# FPGA_Banks.net
KiCad netlist of a schematic drawn in Altium Designer
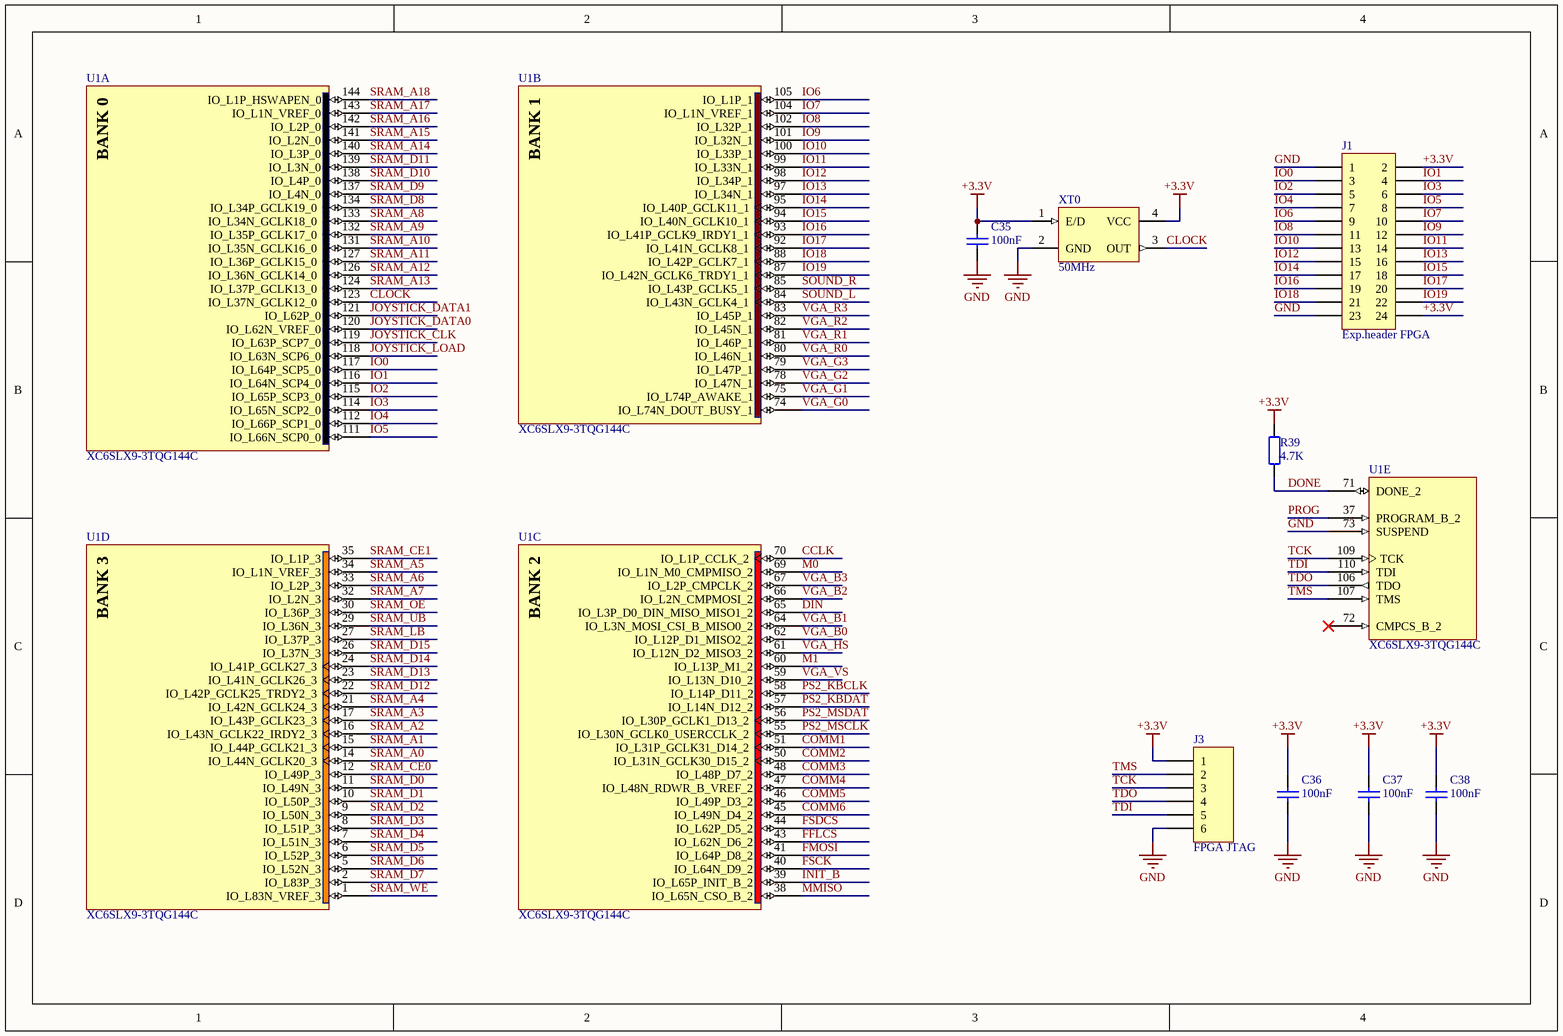
[diagram p0: FPGA Banks.SchDoc]

(export (version "E")
  (design (tool "Eeschema 10.0.6"))
  (components
    (comp (ref "C35")
      (value "100nF")
      (footprint "6-0805_n")
      (description "Capacitor")
      (fields (field (name "Comment") "Cap") (field (name "PUBLISHER") "Altium Limited"))
      (libsource (lib "Miscellaneous Devices") (part "Cap"))
    )
    (comp (ref "C36")
      (value "100nF")
      (footprint "6-0805_n")
      (description "Capacitor")
      (fields (field (name "Comment") "Cap") (field (name "PUBLISHER") "Altium Limited"))
      (libsource (lib "Miscellaneous Devices") (part "Cap"))
    )
    (comp (ref "C37")
      (value "100nF")
      (footprint "6-0805_n")
      (description "Capacitor")
      (fields (field (name "Comment") "Cap") (field (name "PUBLISHER") "Altium Limited"))
      (libsource (lib "Miscellaneous Devices") (part "Cap"))
    )
    (comp (ref "C38")
      (value "100nF")
      (footprint "6-0805_n")
      (description "Capacitor")
      (fields (field (name "Comment") "Cap") (field (name "PUBLISHER") "Altium Limited"))
      (libsource (lib "Miscellaneous Devices") (part "Cap"))
    )
    (comp (ref "J1")
      (value "Exp.header FPGA")
      (footprint "HDR2X12")
      (description "Header, 12-Pin, Dual row")
      (fields (field (name "PUBLISHER") "Altium Limited"))
      (libsource (lib "Miscellaneous Connectors") (part "Header 12X2"))
    )
    (comp (ref "J3")
      (value "FPGA JTAG")
      (footprint "HDR1X6")
      (description "Header, 6-Pin")
      (fields (field (name "PUBLISHER") "Altium Limited"))
      (libsource (lib "Miscellaneous Connectors") (part "Header 6"))
    )
    (comp (ref "R39")
      (value "4.7K")
      (footprint "6-0805_N")
      (description "Resistor")
      (fields (field (name "Comment") "Res2") (field (name "PUBLISHER") "Altium Limited"))
      (libsource (lib "Miscellaneous Devices") (part "Res2"))
    )
    (comp (ref "U1")
      (value "XC6SLX9-3TQG144C")
      (footprint "TQG144_N")
      (fields (field (name "PUBLISHER") "Altium Limited"))
      (libsource (lib "Xilinx Spartan-6") (part "XC6SLX9-3TQG144C"))
    )
    (comp (ref "XT0")
      (value "50MHz")
      (footprint "Oscillator SMD 7x5mm")
      (fields (field (name "Comment") "Oscillator"))
      (libsource (lib "Passiv") (part "Oscillator"))
    )
  )
  (nets
    (net (code "1") (name "+3.3V") (class "Default")
      (node (ref "C35") (pin "2") (pinfunction "2_2") (pintype "passive"))
      (node (ref "C36") (pin "2") (pinfunction "2_2") (pintype "passive"))
      (node (ref "C37") (pin "2") (pinfunction "2_2") (pintype "passive"))
      (node (ref "C38") (pin "2") (pinfunction "2_2") (pintype "passive"))
      (node (ref "J1") (pin "2") (pinfunction "2_2") (pintype "passive"))
      (node (ref "J1") (pin "24") (pinfunction "24_24") (pintype "passive"))
      (node (ref "J3") (pin "1") (pinfunction "1_1") (pintype "passive"))
      (node (ref "R39") (pin "1") (pinfunction "1_1") (pintype "passive"))
      (node (ref "XT0") (pin "1") (pinfunction "E/D_1") (pintype "input"))
      (node (ref "XT0") (pin "4") (pinfunction "VCC_4") (pintype "passive"))
    )
    (net (code "2") (name "/CCLK") (class "Default")
      (node (ref "U1") (pin "70") (pinfunction "IO_L1P_CCLK_2_70") (pintype "bidirectional"))
    )
    (net (code "3") (name "/CLOCK") (class "Default")
      (node (ref "U1") (pin "123") (pinfunction "IO_L37N_GCLK12_0_123") (pintype "bidirectional"))
      (node (ref "XT0") (pin "3") (pinfunction "OUT_3") (pintype "output"))
    )
    (net (code "4") (name "/COMM1") (class "Default")
      (node (ref "U1") (pin "51") (pinfunction "IO_L31P_GCLK31_D14_2_51") (pintype "bidirectional"))
    )
    (net (code "5") (name "/COMM2") (class "Default")
      (node (ref "U1") (pin "50") (pinfunction "IO_L31N_GCLK30_D15_2_50") (pintype "bidirectional"))
    )
    (net (code "6") (name "/COMM3") (class "Default")
      (node (ref "U1") (pin "48") (pinfunction "IO_L48P_D7_2_48") (pintype "bidirectional"))
    )
    (net (code "7") (name "/COMM4") (class "Default")
      (node (ref "U1") (pin "47") (pinfunction "IO_L48N_RDWR_B_VREF_2_47") (pintype "bidirectional"))
    )
    (net (code "8") (name "/COMM5") (class "Default")
      (node (ref "U1") (pin "46") (pinfunction "IO_L49P_D3_2_46") (pintype "bidirectional"))
    )
    (net (code "9") (name "/COMM6") (class "Default")
      (node (ref "U1") (pin "45") (pinfunction "IO_L49N_D4_2_45") (pintype "bidirectional"))
    )
    (net (code "10") (name "/DIN") (class "Default")
      (node (ref "U1") (pin "65") (pinfunction "IO_L3P_D0_DIN_MISO_MISO1_2_65") (pintype "bidirectional"))
    )
    (net (code "11") (name "/DONE") (class "Default")
      (node (ref "R39") (pin "2") (pinfunction "2_2") (pintype "passive"))
      (node (ref "U1") (pin "71") (pinfunction "DONE_2_71") (pintype "bidirectional"))
    )
    (net (code "12") (name "/FFLCS") (class "Default")
      (node (ref "U1") (pin "43") (pinfunction "IO_L62N_D6_2_43") (pintype "bidirectional"))
    )
    (net (code "13") (name "/FMOSI") (class "Default")
      (node (ref "U1") (pin "41") (pinfunction "IO_L64P_D8_2_41") (pintype "bidirectional"))
    )
    (net (code "14") (name "/FSCK") (class "Default")
      (node (ref "U1") (pin "40") (pinfunction "IO_L64N_D9_2_40") (pintype "bidirectional"))
    )
    (net (code "15") (name "/FSDCS") (class "Default")
      (node (ref "U1") (pin "44") (pinfunction "IO_L62P_D5_2_44") (pintype "bidirectional"))
    )
    (net (code "16") (name "/INIT_B") (class "Default")
      (node (ref "U1") (pin "39") (pinfunction "IO_L65P_INIT_B_2_39") (pintype "bidirectional"))
    )
    (net (code "17") (name "/IO0") (class "Default")
      (node (ref "J1") (pin "3") (pinfunction "3_3") (pintype "passive"))
      (node (ref "U1") (pin "117") (pinfunction "IO_L64P_SCP5_0_117") (pintype "bidirectional"))
    )
    (net (code "18") (name "/IO1") (class "Default")
      (node (ref "J1") (pin "4") (pinfunction "4_4") (pintype "passive"))
      (node (ref "U1") (pin "116") (pinfunction "IO_L64N_SCP4_0_116") (pintype "bidirectional"))
    )
    (net (code "19") (name "/IO2") (class "Default")
      (node (ref "J1") (pin "5") (pinfunction "5_5") (pintype "passive"))
      (node (ref "U1") (pin "115") (pinfunction "IO_L65P_SCP3_0_115") (pintype "bidirectional"))
    )
    (net (code "20") (name "/IO3") (class "Default")
      (node (ref "J1") (pin "6") (pinfunction "6_6") (pintype "passive"))
      (node (ref "U1") (pin "114") (pinfunction "IO_L65N_SCP2_0_114") (pintype "bidirectional"))
    )
    (net (code "21") (name "/IO4") (class "Default")
      (node (ref "J1") (pin "7") (pinfunction "7_7") (pintype "passive"))
      (node (ref "U1") (pin "112") (pinfunction "IO_L66P_SCP1_0_112") (pintype "bidirectional"))
    )
    (net (code "22") (name "/IO5") (class "Default")
      (node (ref "J1") (pin "8") (pinfunction "8_8") (pintype "passive"))
      (node (ref "U1") (pin "111") (pinfunction "IO_L66N_SCP0_0_111") (pintype "bidirectional"))
    )
    (net (code "23") (name "/IO6") (class "Default")
      (node (ref "J1") (pin "9") (pinfunction "9_9") (pintype "passive"))
      (node (ref "U1") (pin "105") (pinfunction "IO_L1P_1_105") (pintype "bidirectional"))
    )
    (net (code "24") (name "/IO7") (class "Default")
      (node (ref "J1") (pin "10") (pinfunction "10_10") (pintype "passive"))
      (node (ref "U1") (pin "104") (pinfunction "IO_L1N_VREF_1_104") (pintype "bidirectional"))
    )
    (net (code "25") (name "/IO8") (class "Default")
      (node (ref "J1") (pin "11") (pinfunction "11_11") (pintype "passive"))
      (node (ref "U1") (pin "102") (pinfunction "IO_L32P_1_102") (pintype "bidirectional"))
    )
    (net (code "26") (name "/IO9") (class "Default")
      (node (ref "J1") (pin "12") (pinfunction "12_12") (pintype "passive"))
      (node (ref "U1") (pin "101") (pinfunction "IO_L32N_1_101") (pintype "bidirectional"))
    )
    (net (code "27") (name "/IO10") (class "Default")
      (node (ref "J1") (pin "13") (pinfunction "13_13") (pintype "passive"))
      (node (ref "U1") (pin "100") (pinfunction "IO_L33P_1_100") (pintype "bidirectional"))
    )
    (net (code "28") (name "/IO11") (class "Default")
      (node (ref "J1") (pin "14") (pinfunction "14_14") (pintype "passive"))
      (node (ref "U1") (pin "99") (pinfunction "IO_L33N_1_99") (pintype "bidirectional"))
    )
    (net (code "29") (name "/IO12") (class "Default")
      (node (ref "J1") (pin "15") (pinfunction "15_15") (pintype "passive"))
      (node (ref "U1") (pin "98") (pinfunction "IO_L34P_1_98") (pintype "bidirectional"))
    )
    (net (code "30") (name "/IO13") (class "Default")
      (node (ref "J1") (pin "16") (pinfunction "16_16") (pintype "passive"))
      (node (ref "U1") (pin "97") (pinfunction "IO_L34N_1_97") (pintype "bidirectional"))
    )
    (net (code "31") (name "/IO14") (class "Default")
      (node (ref "J1") (pin "17") (pinfunction "17_17") (pintype "passive"))
      (node (ref "U1") (pin "95") (pinfunction "IO_L40P_GCLK11_1_95") (pintype "bidirectional"))
    )
    (net (code "32") (name "/IO15") (class "Default")
      (node (ref "J1") (pin "18") (pinfunction "18_18") (pintype "passive"))
      (node (ref "U1") (pin "94") (pinfunction "IO_L40N_GCLK10_1_94") (pintype "bidirectional"))
    )
    (net (code "33") (name "/IO16") (class "Default")
      (node (ref "J1") (pin "19") (pinfunction "19_19") (pintype "passive"))
      (node (ref "U1") (pin "93") (pinfunction "IO_L41P_GCLK9_IRDY1_1_93") (pintype "bidirectional"))
    )
    (net (code "34") (name "/IO17") (class "Default")
      (node (ref "J1") (pin "20") (pinfunction "20_20") (pintype "passive"))
      (node (ref "U1") (pin "92") (pinfunction "IO_L41N_GCLK8_1_92") (pintype "bidirectional"))
    )
    (net (code "35") (name "/IO18") (class "Default")
      (node (ref "J1") (pin "21") (pinfunction "21_21") (pintype "passive"))
      (node (ref "U1") (pin "88") (pinfunction "IO_L42P_GCLK7_1_88") (pintype "bidirectional"))
    )
    (net (code "36") (name "/IO19") (class "Default")
      (node (ref "J1") (pin "22") (pinfunction "22_22") (pintype "passive"))
      (node (ref "U1") (pin "87") (pinfunction "IO_L42N_GCLK6_TRDY1_1_87") (pintype "bidirectional"))
    )
    (net (code "37") (name "/JOYSTICK_CLK") (class "Default")
      (node (ref "U1") (pin "119") (pinfunction "IO_L63P_SCP7_0_119") (pintype "bidirectional"))
    )
    (net (code "38") (name "/JOYSTICK_DATA0") (class "Default")
      (node (ref "U1") (pin "120") (pinfunction "IO_L62N_VREF_0_120") (pintype "bidirectional"))
    )
    (net (code "39") (name "/JOYSTICK_DATA1") (class "Default")
      (node (ref "U1") (pin "121") (pinfunction "IO_L62P_0_121") (pintype "bidirectional"))
    )
    (net (code "40") (name "/JOYSTICK_LOAD") (class "Default")
      (node (ref "U1") (pin "118") (pinfunction "IO_L63N_SCP6_0_118") (pintype "bidirectional"))
    )
    (net (code "41") (name "/M0") (class "Default")
      (node (ref "U1") (pin "69") (pinfunction "IO_L1N_M0_CMPMISO_2_69") (pintype "bidirectional"))
    )
    (net (code "42") (name "/M1") (class "Default")
      (node (ref "U1") (pin "60") (pinfunction "IO_L13P_M1_2_60") (pintype "bidirectional"))
    )
    (net (code "43") (name "/MMISO") (class "Default")
      (node (ref "U1") (pin "38") (pinfunction "IO_L65N_CSO_B_2_38") (pintype "bidirectional"))
    )
    (net (code "44") (name "/PROG") (class "Default")
      (node (ref "U1") (pin "37") (pinfunction "PROGRAM_B_2_37") (pintype "input"))
    )
    (net (code "45") (name "/PS2_KBCLK") (class "Default")
      (node (ref "U1") (pin "58") (pinfunction "IO_L14P_D11_2_58") (pintype "bidirectional"))
    )
    (net (code "46") (name "/PS2_KBDAT") (class "Default")
      (node (ref "U1") (pin "57") (pinfunction "IO_L14N_D12_2_57") (pintype "bidirectional"))
    )
    (net (code "47") (name "/PS2_MSCLK") (class "Default")
      (node (ref "U1") (pin "55") (pinfunction "IO_L30N_GCLK0_USERCCLK_2_55") (pintype "bidirectional"))
    )
    (net (code "48") (name "/PS2_MSDAT") (class "Default")
      (node (ref "U1") (pin "56") (pinfunction "IO_L30P_GCLK1_D13_2_56") (pintype "bidirectional"))
    )
    (net (code "49") (name "/SOUND_L") (class "Default")
      (node (ref "U1") (pin "84") (pinfunction "IO_L43N_GCLK4_1_84") (pintype "bidirectional"))
    )
    (net (code "50") (name "/SOUND_R") (class "Default")
      (node (ref "U1") (pin "85") (pinfunction "IO_L43P_GCLK5_1_85") (pintype "bidirectional"))
    )
    (net (code "51") (name "/SRAM_A0") (class "Default")
      (node (ref "U1") (pin "14") (pinfunction "IO_L44N_GCLK20_3_14") (pintype "bidirectional"))
    )
    (net (code "52") (name "/SRAM_A1") (class "Default")
      (node (ref "U1") (pin "15") (pinfunction "IO_L44P_GCLK21_3_15") (pintype "bidirectional"))
    )
    (net (code "53") (name "/SRAM_A2") (class "Default")
      (node (ref "U1") (pin "16") (pinfunction "IO_L43N_GCLK22_IRDY2_3_16") (pintype "bidirectional"))
    )
    (net (code "54") (name "/SRAM_A3") (class "Default")
      (node (ref "U1") (pin "17") (pinfunction "IO_L43P_GCLK23_3_17") (pintype "bidirectional"))
    )
    (net (code "55") (name "/SRAM_A4") (class "Default")
      (node (ref "U1") (pin "21") (pinfunction "IO_L42N_GCLK24_3_21") (pintype "bidirectional"))
    )
    (net (code "56") (name "/SRAM_A5") (class "Default")
      (node (ref "U1") (pin "34") (pinfunction "IO_L1N_VREF_3_34") (pintype "bidirectional"))
    )
    (net (code "57") (name "/SRAM_A6") (class "Default")
      (node (ref "U1") (pin "33") (pinfunction "IO_L2P_3_33") (pintype "bidirectional"))
    )
    (net (code "58") (name "/SRAM_A7") (class "Default")
      (node (ref "U1") (pin "32") (pinfunction "IO_L2N_3_32") (pintype "bidirectional"))
    )
    (net (code "59") (name "/SRAM_A8") (class "Default")
      (node (ref "U1") (pin "133") (pinfunction "IO_L34N_GCLK18_0_133") (pintype "bidirectional"))
    )
    (net (code "60") (name "/SRAM_A9") (class "Default")
      (node (ref "U1") (pin "132") (pinfunction "IO_L35P_GCLK17_0_132") (pintype "bidirectional"))
    )
    (net (code "61") (name "/SRAM_A10") (class "Default")
      (node (ref "U1") (pin "131") (pinfunction "IO_L35N_GCLK16_0_131") (pintype "bidirectional"))
    )
    (net (code "62") (name "/SRAM_A11") (class "Default")
      (node (ref "U1") (pin "127") (pinfunction "IO_L36P_GCLK15_0_127") (pintype "bidirectional"))
    )
    (net (code "63") (name "/SRAM_A12") (class "Default")
      (node (ref "U1") (pin "126") (pinfunction "IO_L36N_GCLK14_0_126") (pintype "bidirectional"))
    )
    (net (code "64") (name "/SRAM_A13") (class "Default")
      (node (ref "U1") (pin "124") (pinfunction "IO_L37P_GCLK13_0_124") (pintype "bidirectional"))
    )
    (net (code "65") (name "/SRAM_A14") (class "Default")
      (node (ref "U1") (pin "140") (pinfunction "IO_L3P_0_140") (pintype "bidirectional"))
    )
    (net (code "66") (name "/SRAM_A15") (class "Default")
      (node (ref "U1") (pin "141") (pinfunction "IO_L2N_0_141") (pintype "bidirectional"))
    )
    (net (code "67") (name "/SRAM_A16") (class "Default")
      (node (ref "U1") (pin "142") (pinfunction "IO_L2P_0_142") (pintype "bidirectional"))
    )
    (net (code "68") (name "/SRAM_A17") (class "Default")
      (node (ref "U1") (pin "143") (pinfunction "IO_L1N_VREF_0_143") (pintype "bidirectional"))
    )
    (net (code "69") (name "/SRAM_A18") (class "Default")
      (node (ref "U1") (pin "144") (pinfunction "IO_L1P_HSWAPEN_0_144") (pintype "bidirectional"))
    )
    (net (code "70") (name "/SRAM_CE0") (class "Default")
      (node (ref "U1") (pin "12") (pinfunction "IO_L49P_3_12") (pintype "bidirectional"))
    )
    (net (code "71") (name "/SRAM_CE1") (class "Default")
      (node (ref "U1") (pin "35") (pinfunction "IO_L1P_3_35") (pintype "bidirectional"))
    )
    (net (code "72") (name "/SRAM_D0") (class "Default")
      (node (ref "U1") (pin "11") (pinfunction "IO_L49N_3_11") (pintype "bidirectional"))
    )
    (net (code "73") (name "/SRAM_D1") (class "Default")
      (node (ref "U1") (pin "10") (pinfunction "IO_L50P_3_10") (pintype "bidirectional"))
    )
    (net (code "74") (name "/SRAM_D2") (class "Default")
      (node (ref "U1") (pin "9") (pinfunction "IO_L50N_3_9") (pintype "bidirectional"))
    )
    (net (code "75") (name "/SRAM_D3") (class "Default")
      (node (ref "U1") (pin "8") (pinfunction "IO_L51P_3_8") (pintype "bidirectional"))
    )
    (net (code "76") (name "/SRAM_D4") (class "Default")
      (node (ref "U1") (pin "7") (pinfunction "IO_L51N_3_7") (pintype "bidirectional"))
    )
    (net (code "77") (name "/SRAM_D5") (class "Default")
      (node (ref "U1") (pin "6") (pinfunction "IO_L52P_3_6") (pintype "bidirectional"))
    )
    (net (code "78") (name "/SRAM_D6") (class "Default")
      (node (ref "U1") (pin "5") (pinfunction "IO_L52N_3_5") (pintype "bidirectional"))
    )
    (net (code "79") (name "/SRAM_D7") (class "Default")
      (node (ref "U1") (pin "2") (pinfunction "IO_L83P_3_2") (pintype "bidirectional"))
    )
    (net (code "80") (name "/SRAM_D8") (class "Default")
      (node (ref "U1") (pin "134") (pinfunction "IO_L34P_GCLK19_0_134") (pintype "bidirectional"))
    )
    (net (code "81") (name "/SRAM_D9") (class "Default")
      (node (ref "U1") (pin "137") (pinfunction "IO_L4N_0_137") (pintype "bidirectional"))
    )
    (net (code "82") (name "/SRAM_D10") (class "Default")
      (node (ref "U1") (pin "138") (pinfunction "IO_L4P_0_138") (pintype "bidirectional"))
    )
    (net (code "83") (name "/SRAM_D11") (class "Default")
      (node (ref "U1") (pin "139") (pinfunction "IO_L3N_0_139") (pintype "bidirectional"))
    )
    (net (code "84") (name "/SRAM_D12") (class "Default")
      (node (ref "U1") (pin "22") (pinfunction "IO_L42P_GCLK25_TRDY2_3_22") (pintype "bidirectional"))
    )
    (net (code "85") (name "/SRAM_D13") (class "Default")
      (node (ref "U1") (pin "23") (pinfunction "IO_L41N_GCLK26_3_23") (pintype "bidirectional"))
    )
    (net (code "86") (name "/SRAM_D14") (class "Default")
      (node (ref "U1") (pin "24") (pinfunction "IO_L41P_GCLK27_3_24") (pintype "bidirectional"))
    )
    (net (code "87") (name "/SRAM_D15") (class "Default")
      (node (ref "U1") (pin "26") (pinfunction "IO_L37N_3_26") (pintype "bidirectional"))
    )
    (net (code "88") (name "/SRAM_LB") (class "Default")
      (node (ref "U1") (pin "27") (pinfunction "IO_L37P_3_27") (pintype "bidirectional"))
    )
    (net (code "89") (name "/SRAM_OE") (class "Default")
      (node (ref "U1") (pin "30") (pinfunction "IO_L36P_3_30") (pintype "bidirectional"))
    )
    (net (code "90") (name "/SRAM_UB") (class "Default")
      (node (ref "U1") (pin "29") (pinfunction "IO_L36N_3_29") (pintype "bidirectional"))
    )
    (net (code "91") (name "/SRAM_WE") (class "Default")
      (node (ref "U1") (pin "1") (pinfunction "IO_L83N_VREF_3_1") (pintype "bidirectional"))
    )
    (net (code "92") (name "/TCK") (class "Default")
      (node (ref "J3") (pin "3") (pinfunction "3_3") (pintype "passive"))
      (node (ref "U1") (pin "109") (pinfunction "TCK_109") (pintype "input"))
    )
    (net (code "93") (name "/TDI") (class "Default")
      (node (ref "J3") (pin "5") (pinfunction "5_5") (pintype "passive"))
      (node (ref "U1") (pin "110") (pinfunction "TDI_110") (pintype "input"))
    )
    (net (code "94") (name "/TDO") (class "Default")
      (node (ref "J3") (pin "4") (pinfunction "4_4") (pintype "passive"))
      (node (ref "U1") (pin "106") (pinfunction "TDO_106") (pintype "output"))
    )
    (net (code "95") (name "/TMS") (class "Default")
      (node (ref "J3") (pin "2") (pinfunction "2_2") (pintype "passive"))
      (node (ref "U1") (pin "107") (pinfunction "TMS_107") (pintype "input"))
    )
    (net (code "96") (name "/VGA_B0") (class "Default")
      (node (ref "U1") (pin "62") (pinfunction "IO_L12P_D1_MISO2_2_62") (pintype "bidirectional"))
    )
    (net (code "97") (name "/VGA_B1") (class "Default")
      (node (ref "U1") (pin "64") (pinfunction "IO_L3N_MOSI_CSI_B_MISO0_2_64") (pintype "bidirectional"))
    )
    (net (code "98") (name "/VGA_B2") (class "Default")
      (node (ref "U1") (pin "66") (pinfunction "IO_L2N_CMPMOSI_2_66") (pintype "bidirectional"))
    )
    (net (code "99") (name "/VGA_B3") (class "Default")
      (node (ref "U1") (pin "67") (pinfunction "IO_L2P_CMPCLK_2_67") (pintype "bidirectional"))
    )
    (net (code "100") (name "/VGA_G0") (class "Default")
      (node (ref "U1") (pin "74") (pinfunction "IO_L74N_DOUT_BUSY_1_74") (pintype "bidirectional"))
    )
    (net (code "101") (name "/VGA_G1") (class "Default")
      (node (ref "U1") (pin "75") (pinfunction "IO_L74P_AWAKE_1_75") (pintype "bidirectional"))
    )
    (net (code "102") (name "/VGA_G2") (class "Default")
      (node (ref "U1") (pin "78") (pinfunction "IO_L47N_1_78") (pintype "bidirectional"))
    )
    (net (code "103") (name "/VGA_G3") (class "Default")
      (node (ref "U1") (pin "79") (pinfunction "IO_L47P_1_79") (pintype "bidirectional"))
    )
    (net (code "104") (name "/VGA_HS") (class "Default")
      (node (ref "U1") (pin "61") (pinfunction "IO_L12N_D2_MISO3_2_61") (pintype "bidirectional"))
    )
    (net (code "105") (name "/VGA_R0") (class "Default")
      (node (ref "U1") (pin "80") (pinfunction "IO_L46N_1_80") (pintype "bidirectional"))
    )
    (net (code "106") (name "/VGA_R1") (class "Default")
      (node (ref "U1") (pin "81") (pinfunction "IO_L46P_1_81") (pintype "bidirectional"))
    )
    (net (code "107") (name "/VGA_R2") (class "Default")
      (node (ref "U1") (pin "82") (pinfunction "IO_L45N_1_82") (pintype "bidirectional"))
    )
    (net (code "108") (name "/VGA_R3") (class "Default")
      (node (ref "U1") (pin "83") (pinfunction "IO_L45P_1_83") (pintype "bidirectional"))
    )
    (net (code "109") (name "/VGA_VS") (class "Default")
      (node (ref "U1") (pin "59") (pinfunction "IO_L13N_D10_2_59") (pintype "bidirectional"))
    )
    (net (code "110") (name "GND") (class "Default")
      (node (ref "C35") (pin "1") (pinfunction "1_1") (pintype "passive"))
      (node (ref "C36") (pin "1") (pinfunction "1_1") (pintype "passive"))
      (node (ref "C37") (pin "1") (pinfunction "1_1") (pintype "passive"))
      (node (ref "C38") (pin "1") (pinfunction "1_1") (pintype "passive"))
      (node (ref "J1") (pin "1") (pinfunction "1_1") (pintype "passive"))
      (node (ref "J1") (pin "23") (pinfunction "23_23") (pintype "passive"))
      (node (ref "J3") (pin "6") (pinfunction "6_6") (pintype "passive"))
      (node (ref "U1") (pin "73") (pinfunction "SUSPEND_73") (pintype "input"))
      (node (ref "XT0") (pin "2") (pinfunction "GND_2") (pintype "passive"))
    )
    (net (code "111") (name "unconnected-(U1E-CMPCS_B_2-Pad72)") (class "Default")
      (node (ref "U1") (pin "72") (pinfunction "CMPCS_B_2_72") (pintype "input+no_connect"))
    )
  )
)
